# powersensor.net
KiCad netlist of a schematic drawn in EAGLE
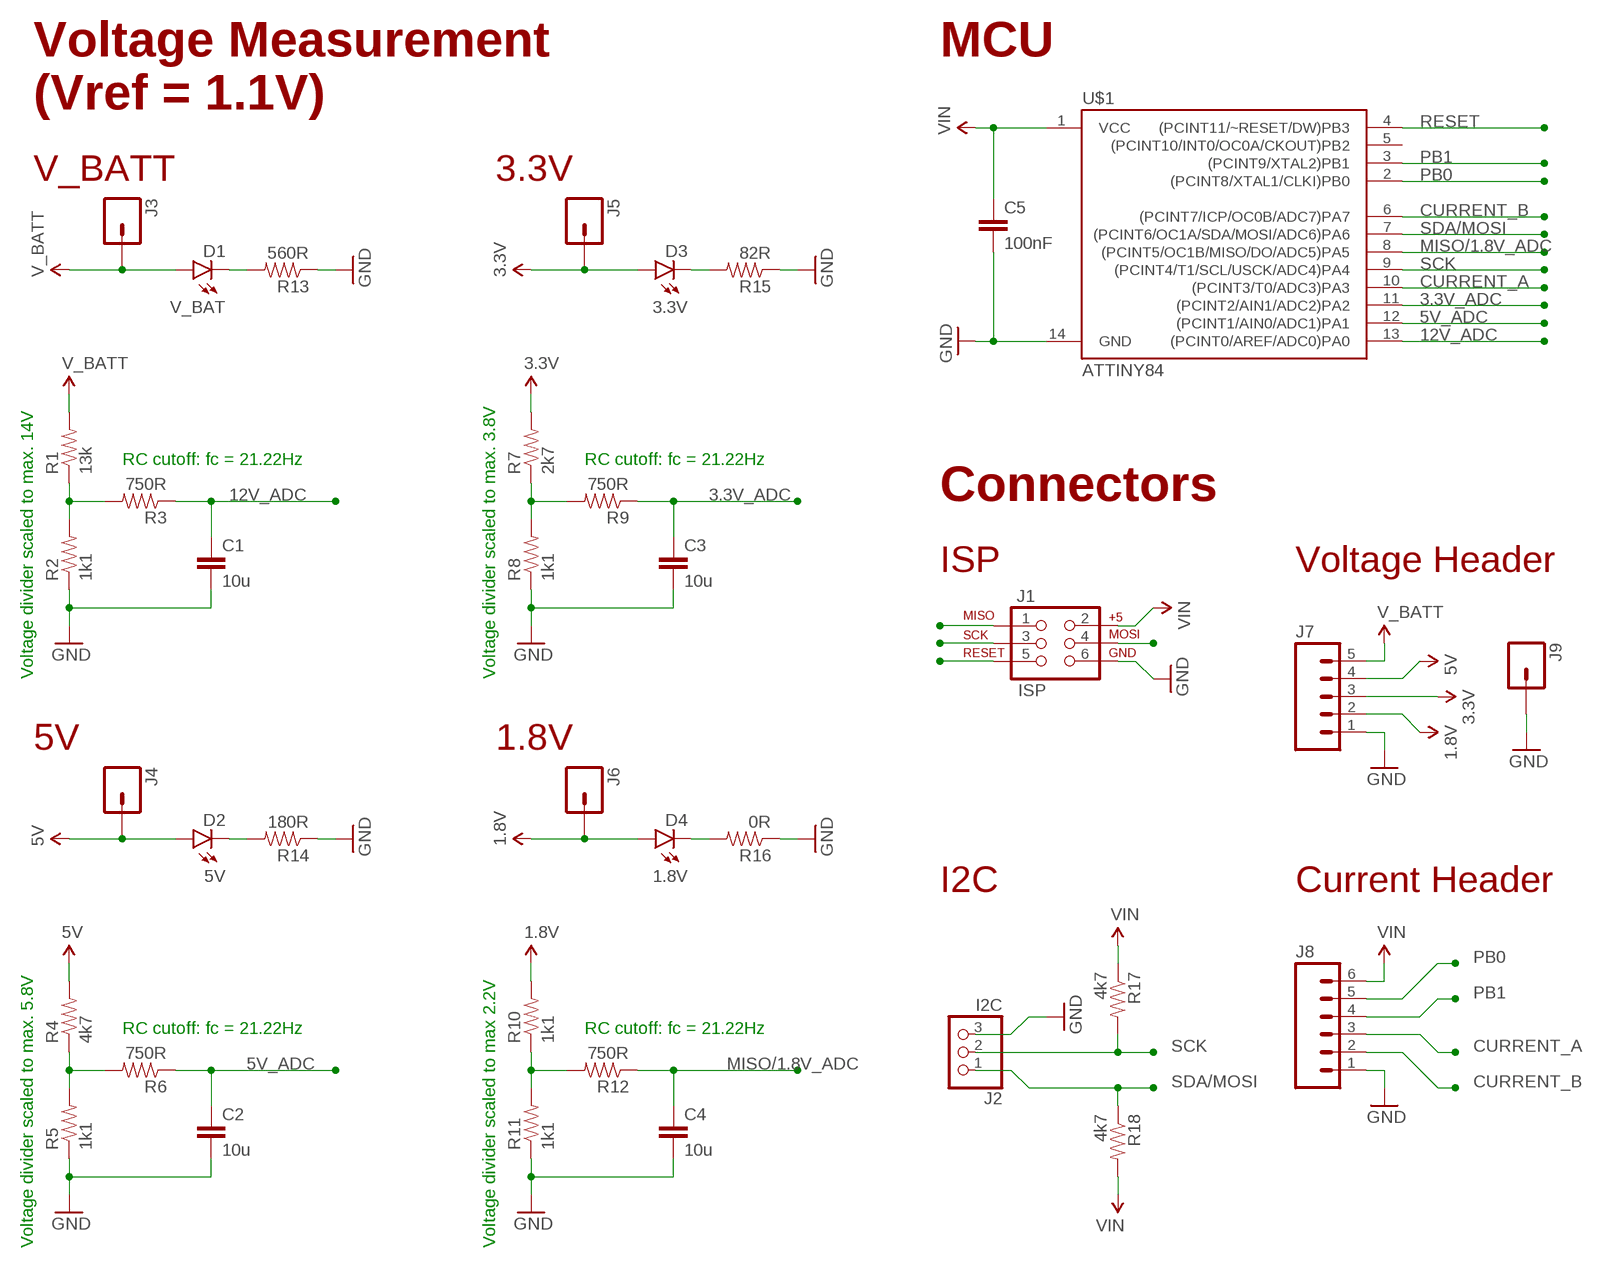
[diagram p0: schematic, sheet 1]

(export (version "E")
  (design (tool "Eeschema 10.0.6"))
  (components
    (comp (ref "C1")
      (value "10u")
      (footprint "eagle-import:0603-CAP")
      (libsource (lib "eagle-import") (part "CAP0603-CAP"))
    )
    (comp (ref "C2")
      (value "10u")
      (footprint "eagle-import:0603-CAP")
      (libsource (lib "eagle-import") (part "CAP0603-CAP"))
    )
    (comp (ref "C3")
      (value "10u")
      (footprint "eagle-import:0603-CAP")
      (libsource (lib "eagle-import") (part "CAP0603-CAP"))
    )
    (comp (ref "C4")
      (value "10u")
      (footprint "eagle-import:0603-CAP")
      (libsource (lib "eagle-import") (part "CAP0603-CAP"))
    )
    (comp (ref "C5")
      (value "100nF")
      (footprint "eagle-import:0603-CAP")
      (libsource (lib "eagle-import") (part "CAP0603-CAP"))
    )
    (comp (ref "D1")
      (value "V_BAT")
      (footprint "eagle-import:LED-0603")
      (libsource (lib "eagle-import") (part "LED0603"))
    )
    (comp (ref "D2")
      (value "5V")
      (footprint "eagle-import:LED-0603")
      (libsource (lib "eagle-import") (part "LED0603"))
    )
    (comp (ref "D3")
      (value "3.3V")
      (footprint "eagle-import:LED-0603")
      (libsource (lib "eagle-import") (part "LED0603"))
    )
    (comp (ref "D4")
      (value "1.8V")
      (footprint "eagle-import:LED-0603")
      (libsource (lib "eagle-import") (part "LED0603"))
    )
    (comp (ref "J1")
      (value "ISP")
      (footprint "eagle-import:2X3")
      (libsource (lib "eagle-import") (part "AVR_SPI_PRG_6PTH"))
    )
    (comp (ref "J2")
      (value "I2C")
      (footprint "eagle-import:1X03_90")
      (libsource (lib "eagle-import") (part "PINHD-1X3/90"))
    )
    (comp (ref "J3")
      (value "M01PTH")
      (footprint "eagle-import:1X01")
      (libsource (lib "eagle-import") (part "M01PTH"))
    )
    (comp (ref "J4")
      (value "M01PTH")
      (footprint "eagle-import:1X01")
      (libsource (lib "eagle-import") (part "M01PTH"))
    )
    (comp (ref "J5")
      (value "M01PTH")
      (footprint "eagle-import:1X01")
      (libsource (lib "eagle-import") (part "M01PTH"))
    )
    (comp (ref "J6")
      (value "M01PTH")
      (footprint "eagle-import:1X01")
      (libsource (lib "eagle-import") (part "M01PTH"))
    )
    (comp (ref "J7")
      (value "M05PTH")
      (footprint "eagle-import:1X05")
      (libsource (lib "eagle-import") (part "M05PTH"))
    )
    (comp (ref "J8")
      (value "M06SILK_FEMALE_PTH")
      (footprint "eagle-import:1X06")
      (libsource (lib "eagle-import") (part "M06SILK_FEMALE_PTH"))
    )
    (comp (ref "J9")
      (value "M01PTH")
      (footprint "eagle-import:1X01")
      (libsource (lib "eagle-import") (part "M01PTH"))
    )
    (comp (ref "R1")
      (value "13k")
      (footprint "eagle-import:0603-RES")
      (libsource (lib "eagle-import") (part "RESISTOR0603-RES"))
    )
    (comp (ref "R2")
      (value "1k1")
      (footprint "eagle-import:0603-RES")
      (libsource (lib "eagle-import") (part "RESISTOR0603-RES"))
    )
    (comp (ref "R3")
      (value "750R")
      (footprint "eagle-import:0603-RES")
      (libsource (lib "eagle-import") (part "RESISTOR0603-RES"))
    )
    (comp (ref "R4")
      (value "4k7")
      (footprint "eagle-import:0603-RES")
      (libsource (lib "eagle-import") (part "RESISTOR0603-RES"))
    )
    (comp (ref "R5")
      (value "1k1")
      (footprint "eagle-import:0603-RES")
      (libsource (lib "eagle-import") (part "RESISTOR0603-RES"))
    )
    (comp (ref "R6")
      (value "750R")
      (footprint "eagle-import:0603-RES")
      (libsource (lib "eagle-import") (part "RESISTOR0603-RES"))
    )
    (comp (ref "R7")
      (value "2k7")
      (footprint "eagle-import:0603-RES")
      (libsource (lib "eagle-import") (part "RESISTOR0603-RES"))
    )
    (comp (ref "R8")
      (value "1k1")
      (footprint "eagle-import:0603-RES")
      (libsource (lib "eagle-import") (part "RESISTOR0603-RES"))
    )
    (comp (ref "R9")
      (value "750R")
      (footprint "eagle-import:0603-RES")
      (libsource (lib "eagle-import") (part "RESISTOR0603-RES"))
    )
    (comp (ref "R10")
      (value "1k1")
      (footprint "eagle-import:0603-RES")
      (libsource (lib "eagle-import") (part "RESISTOR0603-RES"))
    )
    (comp (ref "R11")
      (value "1k1")
      (footprint "eagle-import:0603-RES")
      (libsource (lib "eagle-import") (part "RESISTOR0603-RES"))
    )
    (comp (ref "R12")
      (value "750R")
      (footprint "eagle-import:0603-RES")
      (libsource (lib "eagle-import") (part "RESISTOR0603-RES"))
    )
    (comp (ref "R13")
      (value "560R")
      (footprint "eagle-import:0603-RES")
      (libsource (lib "eagle-import") (part "RESISTOR0603-RES"))
    )
    (comp (ref "R14")
      (value "180R")
      (footprint "eagle-import:0603-RES")
      (libsource (lib "eagle-import") (part "RESISTOR0603-RES"))
    )
    (comp (ref "R15")
      (value "82R")
      (footprint "eagle-import:0603-RES")
      (libsource (lib "eagle-import") (part "RESISTOR0603-RES"))
    )
    (comp (ref "R16")
      (value "0R")
      (footprint "eagle-import:0603-RES")
      (libsource (lib "eagle-import") (part "RESISTOR0603-RES"))
    )
    (comp (ref "R17")
      (value "4k7")
      (footprint "eagle-import:0603-RES")
      (libsource (lib "eagle-import") (part "RESISTOR0603-RES"))
    )
    (comp (ref "R18")
      (value "4k7")
      (footprint "eagle-import:0603-RES")
      (libsource (lib "eagle-import") (part "RESISTOR0603-RES"))
    )
    (comp (ref "U$1")
      (value "ATTINY84")
      (footprint "eagle-import:SO14")
      (libsource (lib "eagle-import") (part "ATTINY84"))
    )
  )
  (nets
    (net (code "1") (name "/3.3V_ADC") (class "Default")
      (node (ref "C3") (pin "1") (pinfunction "1_1") (pintype "passive"))
      (node (ref "R9") (pin "1") (pinfunction "1_1") (pintype "passive"))
      (node (ref "U$1") (pin "11") (pinfunction "(PCINT2/AIN1/ADC2)PA2_11") (pintype "bidirectional"))
    )
    (net (code "2") (name "/5V_ADC") (class "Default")
      (node (ref "C2") (pin "1") (pinfunction "1_1") (pintype "passive"))
      (node (ref "R6") (pin "1") (pinfunction "1_1") (pintype "passive"))
      (node (ref "U$1") (pin "12") (pinfunction "(PCINT1/AIN0/ADC1)PA1_12") (pintype "bidirectional"))
    )
    (net (code "3") (name "/12V_ADC") (class "Default")
      (node (ref "C1") (pin "1") (pinfunction "1_1") (pintype "passive"))
      (node (ref "R3") (pin "1") (pinfunction "1_1") (pintype "passive"))
      (node (ref "U$1") (pin "13") (pinfunction "(PCINT0/AREF/ADC0)PA0_13") (pintype "bidirectional"))
    )
    (net (code "4") (name "/CURRENT_A") (class "Default")
      (node (ref "J8") (pin "3") (pinfunction "3_3") (pintype "passive"))
      (node (ref "U$1") (pin "10") (pinfunction "(PCINT3/T0/ADC3)PA3_10") (pintype "bidirectional"))
    )
    (net (code "5") (name "/CURRENT_B") (class "Default")
      (node (ref "J8") (pin "2") (pinfunction "2_2") (pintype "passive"))
      (node (ref "U$1") (pin "6") (pinfunction "(PCINT7/ICP/OC0B/ADC7)PA7_6") (pintype "bidirectional"))
    )
    (net (code "6") (name "/MISO{slash}1.8V_ADC") (class "Default")
      (node (ref "C4") (pin "1") (pinfunction "1_1") (pintype "passive"))
      (node (ref "J1") (pin "1") (pinfunction "1_1") (pintype "passive"))
      (node (ref "R12") (pin "1") (pinfunction "1_1") (pintype "passive"))
      (node (ref "U$1") (pin "8") (pinfunction "(PCINT5/OC1B/MISO/DO/ADC5)PA5_8") (pintype "bidirectional"))
    )
    (net (code "7") (name "/PB0") (class "Default")
      (node (ref "J8") (pin "5") (pinfunction "5_5") (pintype "passive"))
      (node (ref "U$1") (pin "2") (pinfunction "(PCINT8/XTAL1/CLKI)PB0_2") (pintype "bidirectional"))
    )
    (net (code "8") (name "/PB1") (class "Default")
      (node (ref "J8") (pin "4") (pinfunction "4_4") (pintype "passive"))
      (node (ref "U$1") (pin "3") (pinfunction "(PCINT9/XTAL2)PB1_3") (pintype "bidirectional"))
    )
    (net (code "9") (name "/RESET") (class "Default")
      (node (ref "J1") (pin "5") (pinfunction "5_5") (pintype "passive"))
      (node (ref "U$1") (pin "4") (pinfunction "(PCINT11/~{RESET/DW})PB3_4") (pintype "bidirectional"))
    )
    (net (code "10") (name "/SCK") (class "Default")
      (node (ref "J1") (pin "3") (pinfunction "3_3") (pintype "passive"))
      (node (ref "J2") (pin "2") (pinfunction "2_2") (pintype "passive"))
      (node (ref "R17") (pin "2") (pinfunction "2_2") (pintype "passive"))
      (node (ref "U$1") (pin "9") (pinfunction "(PCINT4/T1/SCL/USCK/ADC4)PA4_9") (pintype "bidirectional"))
    )
    (net (code "11") (name "/SDA{slash}MOSI") (class "Default")
      (node (ref "J1") (pin "4") (pinfunction "4_4") (pintype "passive"))
      (node (ref "J2") (pin "1") (pinfunction "1_1") (pintype "passive"))
      (node (ref "R18") (pin "1") (pinfunction "1_1") (pintype "passive"))
      (node (ref "U$1") (pin "7") (pinfunction "(PCINT6/OC1A/SDA/MOSI/ADC6)PA6_7") (pintype "bidirectional"))
    )
    (net (code "12") (name "1.8V") (class "Default")
      (node (ref "D4") (pin "A") (pinfunction "A_A") (pintype "passive"))
      (node (ref "J6") (pin "1") (pinfunction "1_1") (pintype "passive"))
      (node (ref "J7") (pin "2") (pinfunction "2_2") (pintype "passive"))
      (node (ref "R10") (pin "2") (pinfunction "2_2") (pintype "passive"))
    )
    (net (code "13") (name "3.3V") (class "Default")
      (node (ref "D3") (pin "A") (pinfunction "A_A") (pintype "passive"))
      (node (ref "J5") (pin "1") (pinfunction "1_1") (pintype "passive"))
      (node (ref "J7") (pin "3") (pinfunction "3_3") (pintype "passive"))
      (node (ref "R7") (pin "2") (pinfunction "2_2") (pintype "passive"))
    )
    (net (code "14") (name "5V") (class "Default")
      (node (ref "D2") (pin "A") (pinfunction "A_A") (pintype "passive"))
      (node (ref "J4") (pin "1") (pinfunction "1_1") (pintype "passive"))
      (node (ref "J7") (pin "4") (pinfunction "4_4") (pintype "passive"))
      (node (ref "R4") (pin "2") (pinfunction "2_2") (pintype "passive"))
    )
    (net (code "15") (name "GND") (class "Default")
      (node (ref "C1") (pin "2") (pinfunction "2_2") (pintype "passive"))
      (node (ref "C2") (pin "2") (pinfunction "2_2") (pintype "passive"))
      (node (ref "C3") (pin "2") (pinfunction "2_2") (pintype "passive"))
      (node (ref "C4") (pin "2") (pinfunction "2_2") (pintype "passive"))
      (node (ref "C5") (pin "2") (pinfunction "2_2") (pintype "passive"))
      (node (ref "J1") (pin "6") (pinfunction "6_6") (pintype "passive"))
      (node (ref "J2") (pin "3") (pinfunction "3_3") (pintype "passive"))
      (node (ref "J7") (pin "1") (pinfunction "1_1") (pintype "passive"))
      (node (ref "J8") (pin "1") (pinfunction "1_1") (pintype "passive"))
      (node (ref "J9") (pin "1") (pinfunction "1_1") (pintype "passive"))
      (node (ref "R11") (pin "1") (pinfunction "1_1") (pintype "passive"))
      (node (ref "R13") (pin "1") (pinfunction "1_1") (pintype "passive"))
      (node (ref "R14") (pin "1") (pinfunction "1_1") (pintype "passive"))
      (node (ref "R15") (pin "1") (pinfunction "1_1") (pintype "passive"))
      (node (ref "R16") (pin "1") (pinfunction "1_1") (pintype "passive"))
      (node (ref "R2") (pin "1") (pinfunction "1_1") (pintype "passive"))
      (node (ref "R5") (pin "1") (pinfunction "1_1") (pintype "passive"))
      (node (ref "R8") (pin "1") (pinfunction "1_1") (pintype "passive"))
      (node (ref "U$1") (pin "14") (pinfunction "GND_14") (pintype "bidirectional"))
    )
    (net (code "16") (name "Net-(D1-PadC)") (class "Default")
      (node (ref "D1") (pin "C") (pinfunction "C_C") (pintype "passive"))
      (node (ref "R13") (pin "2") (pinfunction "2_2") (pintype "passive"))
    )
    (net (code "17") (name "Net-(D2-PadC)") (class "Default")
      (node (ref "D2") (pin "C") (pinfunction "C_C") (pintype "passive"))
      (node (ref "R14") (pin "2") (pinfunction "2_2") (pintype "passive"))
    )
    (net (code "18") (name "Net-(D3-PadC)") (class "Default")
      (node (ref "D3") (pin "C") (pinfunction "C_C") (pintype "passive"))
      (node (ref "R15") (pin "2") (pinfunction "2_2") (pintype "passive"))
    )
    (net (code "19") (name "Net-(D4-PadC)") (class "Default")
      (node (ref "D4") (pin "C") (pinfunction "C_C") (pintype "passive"))
      (node (ref "R16") (pin "2") (pinfunction "2_2") (pintype "passive"))
    )
    (net (code "20") (name "Net-(R1-Pad1)") (class "Default")
      (node (ref "R1") (pin "1") (pinfunction "1_1") (pintype "passive"))
      (node (ref "R2") (pin "2") (pinfunction "2_2") (pintype "passive"))
      (node (ref "R3") (pin "2") (pinfunction "2_2") (pintype "passive"))
    )
    (net (code "21") (name "Net-(R4-Pad1)") (class "Default")
      (node (ref "R4") (pin "1") (pinfunction "1_1") (pintype "passive"))
      (node (ref "R5") (pin "2") (pinfunction "2_2") (pintype "passive"))
      (node (ref "R6") (pin "2") (pinfunction "2_2") (pintype "passive"))
    )
    (net (code "22") (name "Net-(R7-Pad1)") (class "Default")
      (node (ref "R7") (pin "1") (pinfunction "1_1") (pintype "passive"))
      (node (ref "R8") (pin "2") (pinfunction "2_2") (pintype "passive"))
      (node (ref "R9") (pin "2") (pinfunction "2_2") (pintype "passive"))
    )
    (net (code "23") (name "Net-(R10-Pad1)") (class "Default")
      (node (ref "R10") (pin "1") (pinfunction "1_1") (pintype "passive"))
      (node (ref "R11") (pin "2") (pinfunction "2_2") (pintype "passive"))
      (node (ref "R12") (pin "2") (pinfunction "2_2") (pintype "passive"))
    )
    (net (code "24") (name "VIN") (class "Default")
      (node (ref "C5") (pin "1") (pinfunction "1_1") (pintype "passive"))
      (node (ref "J1") (pin "2") (pinfunction "2_2") (pintype "passive"))
      (node (ref "J8") (pin "6") (pinfunction "6_6") (pintype "passive"))
      (node (ref "R17") (pin "1") (pinfunction "1_1") (pintype "passive"))
      (node (ref "R18") (pin "2") (pinfunction "2_2") (pintype "passive"))
      (node (ref "U$1") (pin "1") (pinfunction "VCC_1") (pintype "bidirectional"))
    )
    (net (code "25") (name "V_BATT") (class "Default")
      (node (ref "D1") (pin "A") (pinfunction "A_A") (pintype "passive"))
      (node (ref "J3") (pin "1") (pinfunction "1_1") (pintype "passive"))
      (node (ref "J7") (pin "5") (pinfunction "5_5") (pintype "passive"))
      (node (ref "R1") (pin "2") (pinfunction "2_2") (pintype "passive"))
    )
    (net (code "26") (name "unconnected-(U$1-(PCINT10{slash}INT0{slash}OC0A{slash}CKOUT)PB2-Pad5)") (class "Default")
      (node (ref "U$1") (pin "5") (pinfunction "(PCINT10/INT0/OC0A/CKOUT)PB2_5") (pintype "bidirectional"))
    )
  )
)
